# Sheet1.net
KiCad netlist of a schematic drawn in Altium Designer
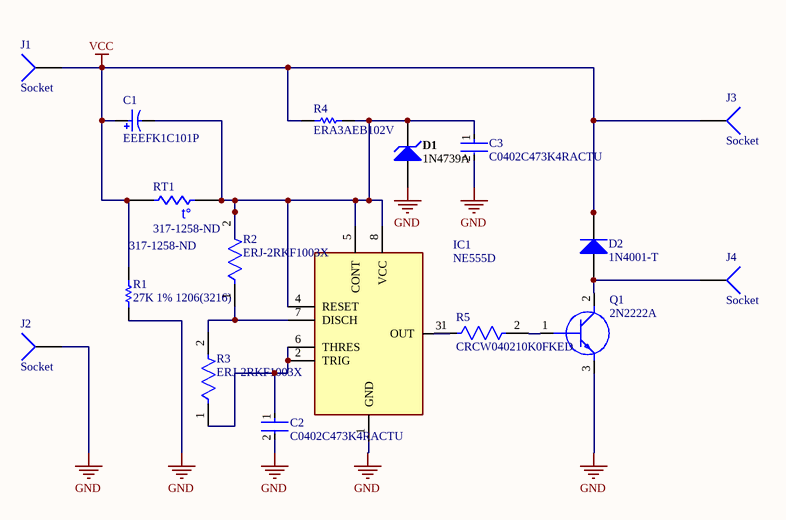
[diagram p0: Sheet1.SchDoc]

(export (version "E")
  (design (tool "Eeschema 10.0.6"))
  (components
    (comp (ref "C1")
      (value "EEEFK1C101P")
      (footprint "PNSC-EEEFK1C101P_L")
      (fields (field (name "MANUFACTURER") "Panasonic"))
      (libsource (lib "Altium Content Vault") (part "CAP-P-2"))
    )
    (comp (ref "C2")
      (value "C0402C473K4RACTU")
      (footprint "FP-C0402-BB-MFG")
      (description "C0402 47,000 pF X7R 10.00% 16 V")
      (fields (field (name "TOLERANCE") "0.1"))
      (libsource (lib "Altium Content Vault") (part "b4654b650e69147ec39a6b967a45e02"))
    )
    (comp (ref "C3")
      (value "C0402C473K4RACTU")
      (footprint "FP-C0402-BB-MFG")
      (description "C0402 47,000 pF X7R 10.00% 16 V")
      (fields (field (name "TOLERANCE") "0.1"))
      (libsource (lib "Altium Content Vault") (part "b4654b650e69147ec39a6b967a45e02"))
    )
    (comp (ref "D1")
      (value "1N4739A")
      (footprint "FAIR-DO-41-2_V")
      (description "Zener Diode, 9.1V, 1W, 5%, -65 to 200 degC, 2-Pin DO-41, Body 2.72 x 5.2 mm, RoHS")
      (fields (field (name "TOLERANCE") "5%") (field (name "MANUFACTURER") "Fairchild Semiconductor"))
      (libsource (lib "Altium Content Vault") (part "FAIR-DZEN-A1K2-2"))
    )
    (comp (ref "D2")
      (value "1N4001-T")
      (footprint "DIOD-DO-41-P-2_V")
      (description "1.0 A Rectifier, 15 pF, 50 V, -65 to 150 degC, 2-Pin DO-41 Plastic, RoHS, Tape and Reel")
      (fields (field (name "MANUFACTURER") "Diodes Inc"))
      (libsource (lib "Altium Content Vault") (part "DIOD-D-A1K2-2"))
    )
    (comp (ref "IC1")
      (value "NE555D")
      (footprint "SamacSys:SOIC127P600X175-8N")
      (description "Integrated Circuit")
      (fields (field (name "MOUSER PART NUMBER") "595-NE555D"))
      (libsource (lib "*") (part "NE555D"))
    )
    (comp (ref "J1")
      (value "Socket")
      (footprint "PIN1")
      (fields (field (name "PUBLISHER") "Altium Limited"))
      (libsource (lib "Miscellaneous Connectors") (part "Socket"))
    )
    (comp (ref "J2")
      (value "Socket")
      (footprint "PIN1")
      (fields (field (name "PUBLISHER") "Altium Limited"))
      (libsource (lib "Miscellaneous Connectors") (part "Socket"))
    )
    (comp (ref "J3")
      (value "Socket")
      (footprint "PIN1")
      (fields (field (name "PUBLISHER") "Altium Limited"))
      (libsource (lib "Miscellaneous Connectors") (part "Socket"))
    )
    (comp (ref "J4")
      (value "Socket")
      (footprint "PIN1")
      (fields (field (name "PUBLISHER") "Altium Limited"))
      (libsource (lib "Miscellaneous Connectors") (part "Socket"))
    )
    (comp (ref "Q1")
      (value "2N2222A")
      (footprint "SamacSys:TO-18_4")
      (description "Transistor BJT NPN")
      (fields (field (name "MOUSER PART NUMBER") "511-2N2222A"))
      (libsource (lib "*") (part "2N2222A"))
    )
    (comp (ref "R1")
      (value "27K 1% 1206(3216)")
      (footprint "RESC1206(3216)_M")
      (description "27K 0.25W 1% 1206 (3216 Metric)  SMD")
      (fields (field (name "POWER") "0.25 W") (field (name "TOLERANCE") "1 %"))
      (libsource (lib "Altium Content Vault") (part "RES"))
    )
    (comp (ref "R2")
      (value "ERJ-2RKF1003X")
      (footprint "FP-ERJ2RK-IPC_C")
      (description "RES SMD 100K OHM 1% 1/10W 0402")
      (fields (field (name "TOLERANCE") "1%"))
      (libsource (lib "Altium Content Vault") (part "1029c3af85768c4190bb7ad29bc67b5"))
    )
    (comp (ref "R3")
      (value "ERJ-2RKF1003X")
      (footprint "FP-ERJ2RK-IPC_C")
      (description "RES SMD 100K OHM 1% 1/10W 0402")
      (fields (field (name "TOLERANCE") "1%"))
      (libsource (lib "Altium Content Vault") (part "1029c3af85768c4190bb7ad29bc67b5"))
    )
    (comp (ref "R4")
      (value "ERA3AEB102V")
      (footprint "RESC1608X55X30LL20T20")
      (fields (field (name "MANUFACTURER") "Panasonic"))
      (libsource (lib "Altium Content Vault") (part "RES"))
    )
    (comp (ref "R5")
      (value "CRCW040210K0FKED")
      (footprint "FP-CRCW0402-e3-MFG")
      (description "RES SMD 10K OHM 1% 1/16W 0402")
      (fields (field (name "TOLERANCE") "1%"))
      (libsource (lib "Altium Content Vault") (part "1029c3af85768c4190bb7ad29bc67b5"))
    )
    (comp (ref "RT1")
      (value "317-1258-ND")
      (footprint "6-0805_N")
      (description "THERMISTOR NTC 10KOHM 3470K BEAD")
      (fields
        (field (name "SUPPLIER PART NUMBER 1") "317-1258-ND")
        (field (name "MANUFACTURER") "Canadian Thermostats")
        (field (name "MANUFACTURER PART NUMBER") "MF52A2103J3470")
        (field (name "PUBLISHER") "Altium Limited")
      )
      (libsource (lib "Miscellaneous Devices") (part "Res Thermal"))
    )
  )
  (nets
    (net (code "1") (name "GND") (class "Default")
      (node (ref "C2") (pin "2") (pinfunction "2_2") (pintype "passive"))
      (node (ref "C3") (pin "2") (pinfunction "2_2") (pintype "passive"))
      (node (ref "D1") (pin "1") (pinfunction "A_1") (pintype "passive"))
      (node (ref "IC1") (pin "1") (pinfunction "GND_1") (pintype "passive"))
      (node (ref "J2") (pin "1") (pinfunction "1_1") (pintype "passive"))
      (node (ref "Q1") (pin "3") (pinfunction "E_3") (pintype "passive"))
      (node (ref "R1") (pin "1") (pinfunction "1_1") (pintype "passive"))
    )
    (net (code "2") (name "Net-(D1-K)") (class "Default")
      (node (ref "C1") (pin "2") (pinfunction "2_2") (pintype "passive"))
      (node (ref "C3") (pin "1") (pinfunction "1_1") (pintype "passive"))
      (node (ref "D1") (pin "2") (pinfunction "K_2") (pintype "passive"))
      (node (ref "IC1") (pin "4") (pinfunction "RESET_4") (pintype "passive"))
      (node (ref "IC1") (pin "5") (pinfunction "CONT_5") (pintype "passive"))
      (node (ref "IC1") (pin "8") (pinfunction "VCC_8") (pintype "passive"))
      (node (ref "R2") (pin "2") (pinfunction "2_2") (pintype "passive"))
      (node (ref "R4") (pin "2") (pinfunction "2_2") (pintype "passive"))
      (node (ref "RT1") (pin "1") (pinfunction "1_1") (pintype "passive"))
    )
    (net (code "3") (name "Net-(D2-A)") (class "Default")
      (node (ref "D2") (pin "1") (pinfunction "A_1") (pintype "passive"))
      (node (ref "J4") (pin "1") (pinfunction "1_1") (pintype "passive"))
      (node (ref "Q1") (pin "2") (pinfunction "C_2") (pintype "passive"))
    )
    (net (code "4") (name "Net-(IC1-DISCH)") (class "Default")
      (node (ref "IC1") (pin "7") (pinfunction "DISCH_7") (pintype "passive"))
      (node (ref "R2") (pin "1") (pinfunction "1_1") (pintype "passive"))
      (node (ref "R3") (pin "2") (pinfunction "2_2") (pintype "passive"))
    )
    (net (code "5") (name "Net-(IC1-OUT)") (class "Default")
      (node (ref "IC1") (pin "3") (pinfunction "OUT_3") (pintype "passive"))
      (node (ref "R5") (pin "1") (pinfunction "1_1") (pintype "passive"))
    )
    (net (code "6") (name "Net-(IC1-THRES)") (class "Default")
      (node (ref "C2") (pin "1") (pinfunction "1_1") (pintype "passive"))
      (node (ref "IC1") (pin "2") (pinfunction "TRIG_2") (pintype "passive"))
      (node (ref "IC1") (pin "6") (pinfunction "THRES_6") (pintype "passive"))
      (node (ref "R3") (pin "1") (pinfunction "1_1") (pintype "passive"))
    )
    (net (code "7") (name "Net-(Q1-B)") (class "Default")
      (node (ref "Q1") (pin "1") (pinfunction "B_1") (pintype "passive"))
      (node (ref "R5") (pin "2") (pinfunction "2_2") (pintype "passive"))
    )
    (net (code "8") (name "VCC") (class "Default")
      (node (ref "C1") (pin "1") (pinfunction "1_1") (pintype "passive"))
      (node (ref "D2") (pin "2") (pinfunction "K_2") (pintype "passive"))
      (node (ref "J1") (pin "1") (pinfunction "1_1") (pintype "passive"))
      (node (ref "J3") (pin "1") (pinfunction "1_1") (pintype "passive"))
      (node (ref "R1") (pin "2") (pinfunction "2_2") (pintype "passive"))
      (node (ref "R4") (pin "1") (pinfunction "1_1") (pintype "passive"))
      (node (ref "RT1") (pin "2") (pinfunction "2_2") (pintype "passive"))
    )
  )
)
